# dcc-a-star32U.net
KiCad netlist of a schematic drawn in EAGLE
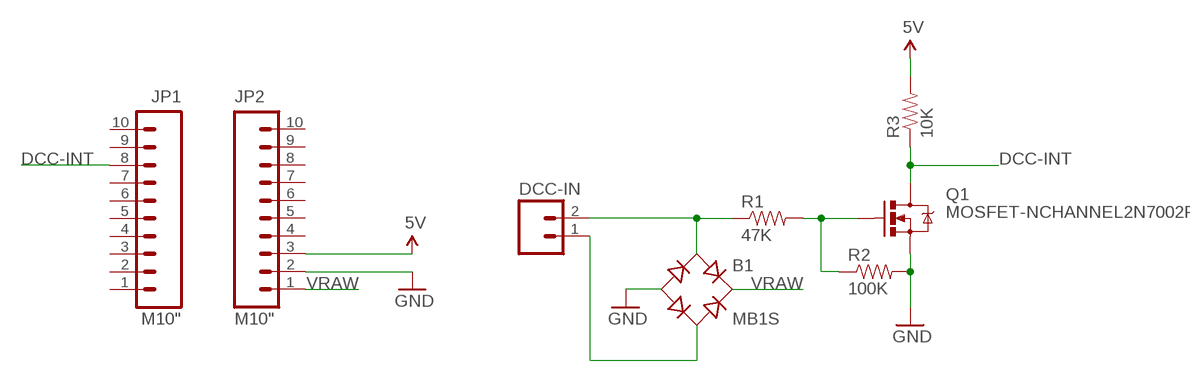
[diagram p0: schematic, sheet 1]

(export (version "E")
  (design (tool "Eeschema 10.0.6"))
  (components
    (comp (ref "B1")
      (value "MB1S")
      (footprint "eagle-import:SOIC-4")
      (libsource (lib "eagle-import") (part "MBS1"))
    )
    (comp (ref "DCC-IN")
      (value "M02-JST-2-PTH-NO_SILK")
      (footprint "eagle-import:JST-2-PTH-NS")
      (libsource (lib "eagle-import") (part "M02-JST-2-PTH-NO_SILK"))
    )
    (comp (ref "JP1")
      (value "M10\"")
      (footprint "eagle-import:1X10")
      (libsource (lib "eagle-import") (part "M10{dblquote}"))
    )
    (comp (ref "JP2")
      (value "M10\"")
      (footprint "eagle-import:1X10")
      (libsource (lib "eagle-import") (part "M10{dblquote}"))
    )
    (comp (ref "Q1")
      (value "MOSFET-NCHANNEL2N7002PW")
      (footprint "eagle-import:SOT323")
      (libsource (lib "eagle-import") (part "MOSFET-NCHANNEL2N7002PW"))
    )
    (comp (ref "R1")
      (value "47K")
      (footprint "eagle-import:0603-RES")
      (libsource (lib "eagle-import") (part "RESISTOR0603-RES"))
    )
    (comp (ref "R2")
      (value "100K")
      (footprint "eagle-import:0603-RES")
      (libsource (lib "eagle-import") (part "RESISTOR0603-RES"))
    )
    (comp (ref "R3")
      (value "10K")
      (footprint "eagle-import:0603-RES")
      (libsource (lib "eagle-import") (part "RESISTOR0603-RES"))
    )
  )
  (nets
    (net (code "1") (name "/DCC-INT") (class "Default")
      (node (ref "JP1") (pin "8") (pinfunction "8_8") (pintype "passive"))
      (node (ref "Q1") (pin "3") (pinfunction "D_3") (pintype "passive"))
      (node (ref "R3") (pin "1") (pinfunction "1_1") (pintype "passive"))
    )
    (net (code "2") (name "/VRAW") (class "Default")
      (node (ref "B1") (pin "+") (pinfunction "+_+") (pintype "passive"))
      (node (ref "JP2") (pin "1") (pinfunction "1_1") (pintype "passive"))
    )
    (net (code "3") (name "5V") (class "Default")
      (node (ref "JP2") (pin "3") (pinfunction "3_3") (pintype "passive"))
      (node (ref "R3") (pin "2") (pinfunction "2_2") (pintype "passive"))
    )
    (net (code "4") (name "GND") (class "Default")
      (node (ref "B1") (pin "-") (pinfunction "-_-") (pintype "passive"))
      (node (ref "JP2") (pin "2") (pinfunction "2_2") (pintype "passive"))
      (node (ref "Q1") (pin "2") (pinfunction "S_2") (pintype "passive"))
      (node (ref "R2") (pin "2") (pinfunction "2_2") (pintype "passive"))
    )
    (net (code "5") (name "Net-(B1-AC1)") (class "Default")
      (node (ref "B1") (pin "~1") (pinfunction "AC1_~1") (pintype "passive"))
      (node (ref "DCC-IN") (pin "2") (pinfunction "2_2") (pintype "passive"))
      (node (ref "R1") (pin "1") (pinfunction "1_1") (pintype "passive"))
    )
    (net (code "6") (name "Net-(B1-AC2)") (class "Default")
      (node (ref "B1") (pin "~2") (pinfunction "AC2_~2") (pintype "passive"))
      (node (ref "DCC-IN") (pin "1") (pinfunction "1_1") (pintype "passive"))
    )
    (net (code "7") (name "Net-(Q1-G)") (class "Default")
      (node (ref "Q1") (pin "1") (pinfunction "G_1") (pintype "passive"))
      (node (ref "R1") (pin "2") (pinfunction "2_2") (pintype "passive"))
      (node (ref "R2") (pin "1") (pinfunction "1_1") (pintype "passive"))
    )
    (net (code "8") (name "unconnected-(JP1-Pad1)") (class "Default")
      (node (ref "JP1") (pin "1") (pinfunction "1_1") (pintype "passive"))
    )
    (net (code "9") (name "unconnected-(JP1-Pad2)") (class "Default")
      (node (ref "JP1") (pin "2") (pinfunction "2_2") (pintype "passive"))
    )
    (net (code "10") (name "unconnected-(JP1-Pad3)") (class "Default")
      (node (ref "JP1") (pin "3") (pinfunction "3_3") (pintype "passive"))
    )
    (net (code "11") (name "unconnected-(JP1-Pad4)") (class "Default")
      (node (ref "JP1") (pin "4") (pinfunction "4_4") (pintype "passive"))
    )
    (net (code "12") (name "unconnected-(JP1-Pad5)") (class "Default")
      (node (ref "JP1") (pin "5") (pinfunction "5_5") (pintype "passive"))
    )
    (net (code "13") (name "unconnected-(JP1-Pad6)") (class "Default")
      (node (ref "JP1") (pin "6") (pinfunction "6_6") (pintype "passive"))
    )
    (net (code "14") (name "unconnected-(JP1-Pad7)") (class "Default")
      (node (ref "JP1") (pin "7") (pinfunction "7_7") (pintype "passive"))
    )
    (net (code "15") (name "unconnected-(JP1-Pad9)") (class "Default")
      (node (ref "JP1") (pin "9") (pinfunction "9_9") (pintype "passive"))
    )
    (net (code "16") (name "unconnected-(JP1-Pad10)") (class "Default")
      (node (ref "JP1") (pin "10") (pinfunction "10_10") (pintype "passive"))
    )
    (net (code "17") (name "unconnected-(JP2-Pad4)") (class "Default")
      (node (ref "JP2") (pin "4") (pinfunction "4_4") (pintype "passive"))
    )
    (net (code "18") (name "unconnected-(JP2-Pad5)") (class "Default")
      (node (ref "JP2") (pin "5") (pinfunction "5_5") (pintype "passive"))
    )
    (net (code "19") (name "unconnected-(JP2-Pad6)") (class "Default")
      (node (ref "JP2") (pin "6") (pinfunction "6_6") (pintype "passive"))
    )
    (net (code "20") (name "unconnected-(JP2-Pad7)") (class "Default")
      (node (ref "JP2") (pin "7") (pinfunction "7_7") (pintype "passive"))
    )
    (net (code "21") (name "unconnected-(JP2-Pad8)") (class "Default")
      (node (ref "JP2") (pin "8") (pinfunction "8_8") (pintype "passive"))
    )
    (net (code "22") (name "unconnected-(JP2-Pad9)") (class "Default")
      (node (ref "JP2") (pin "9") (pinfunction "9_9") (pintype "passive"))
    )
    (net (code "23") (name "unconnected-(JP2-Pad10)") (class "Default")
      (node (ref "JP2") (pin "10") (pinfunction "10_10") (pintype "passive"))
    )
  )
)
